# SCH_NFC-Card_2024-10-10.net
KiCad netlist of a schematic drawn in EasyEDA
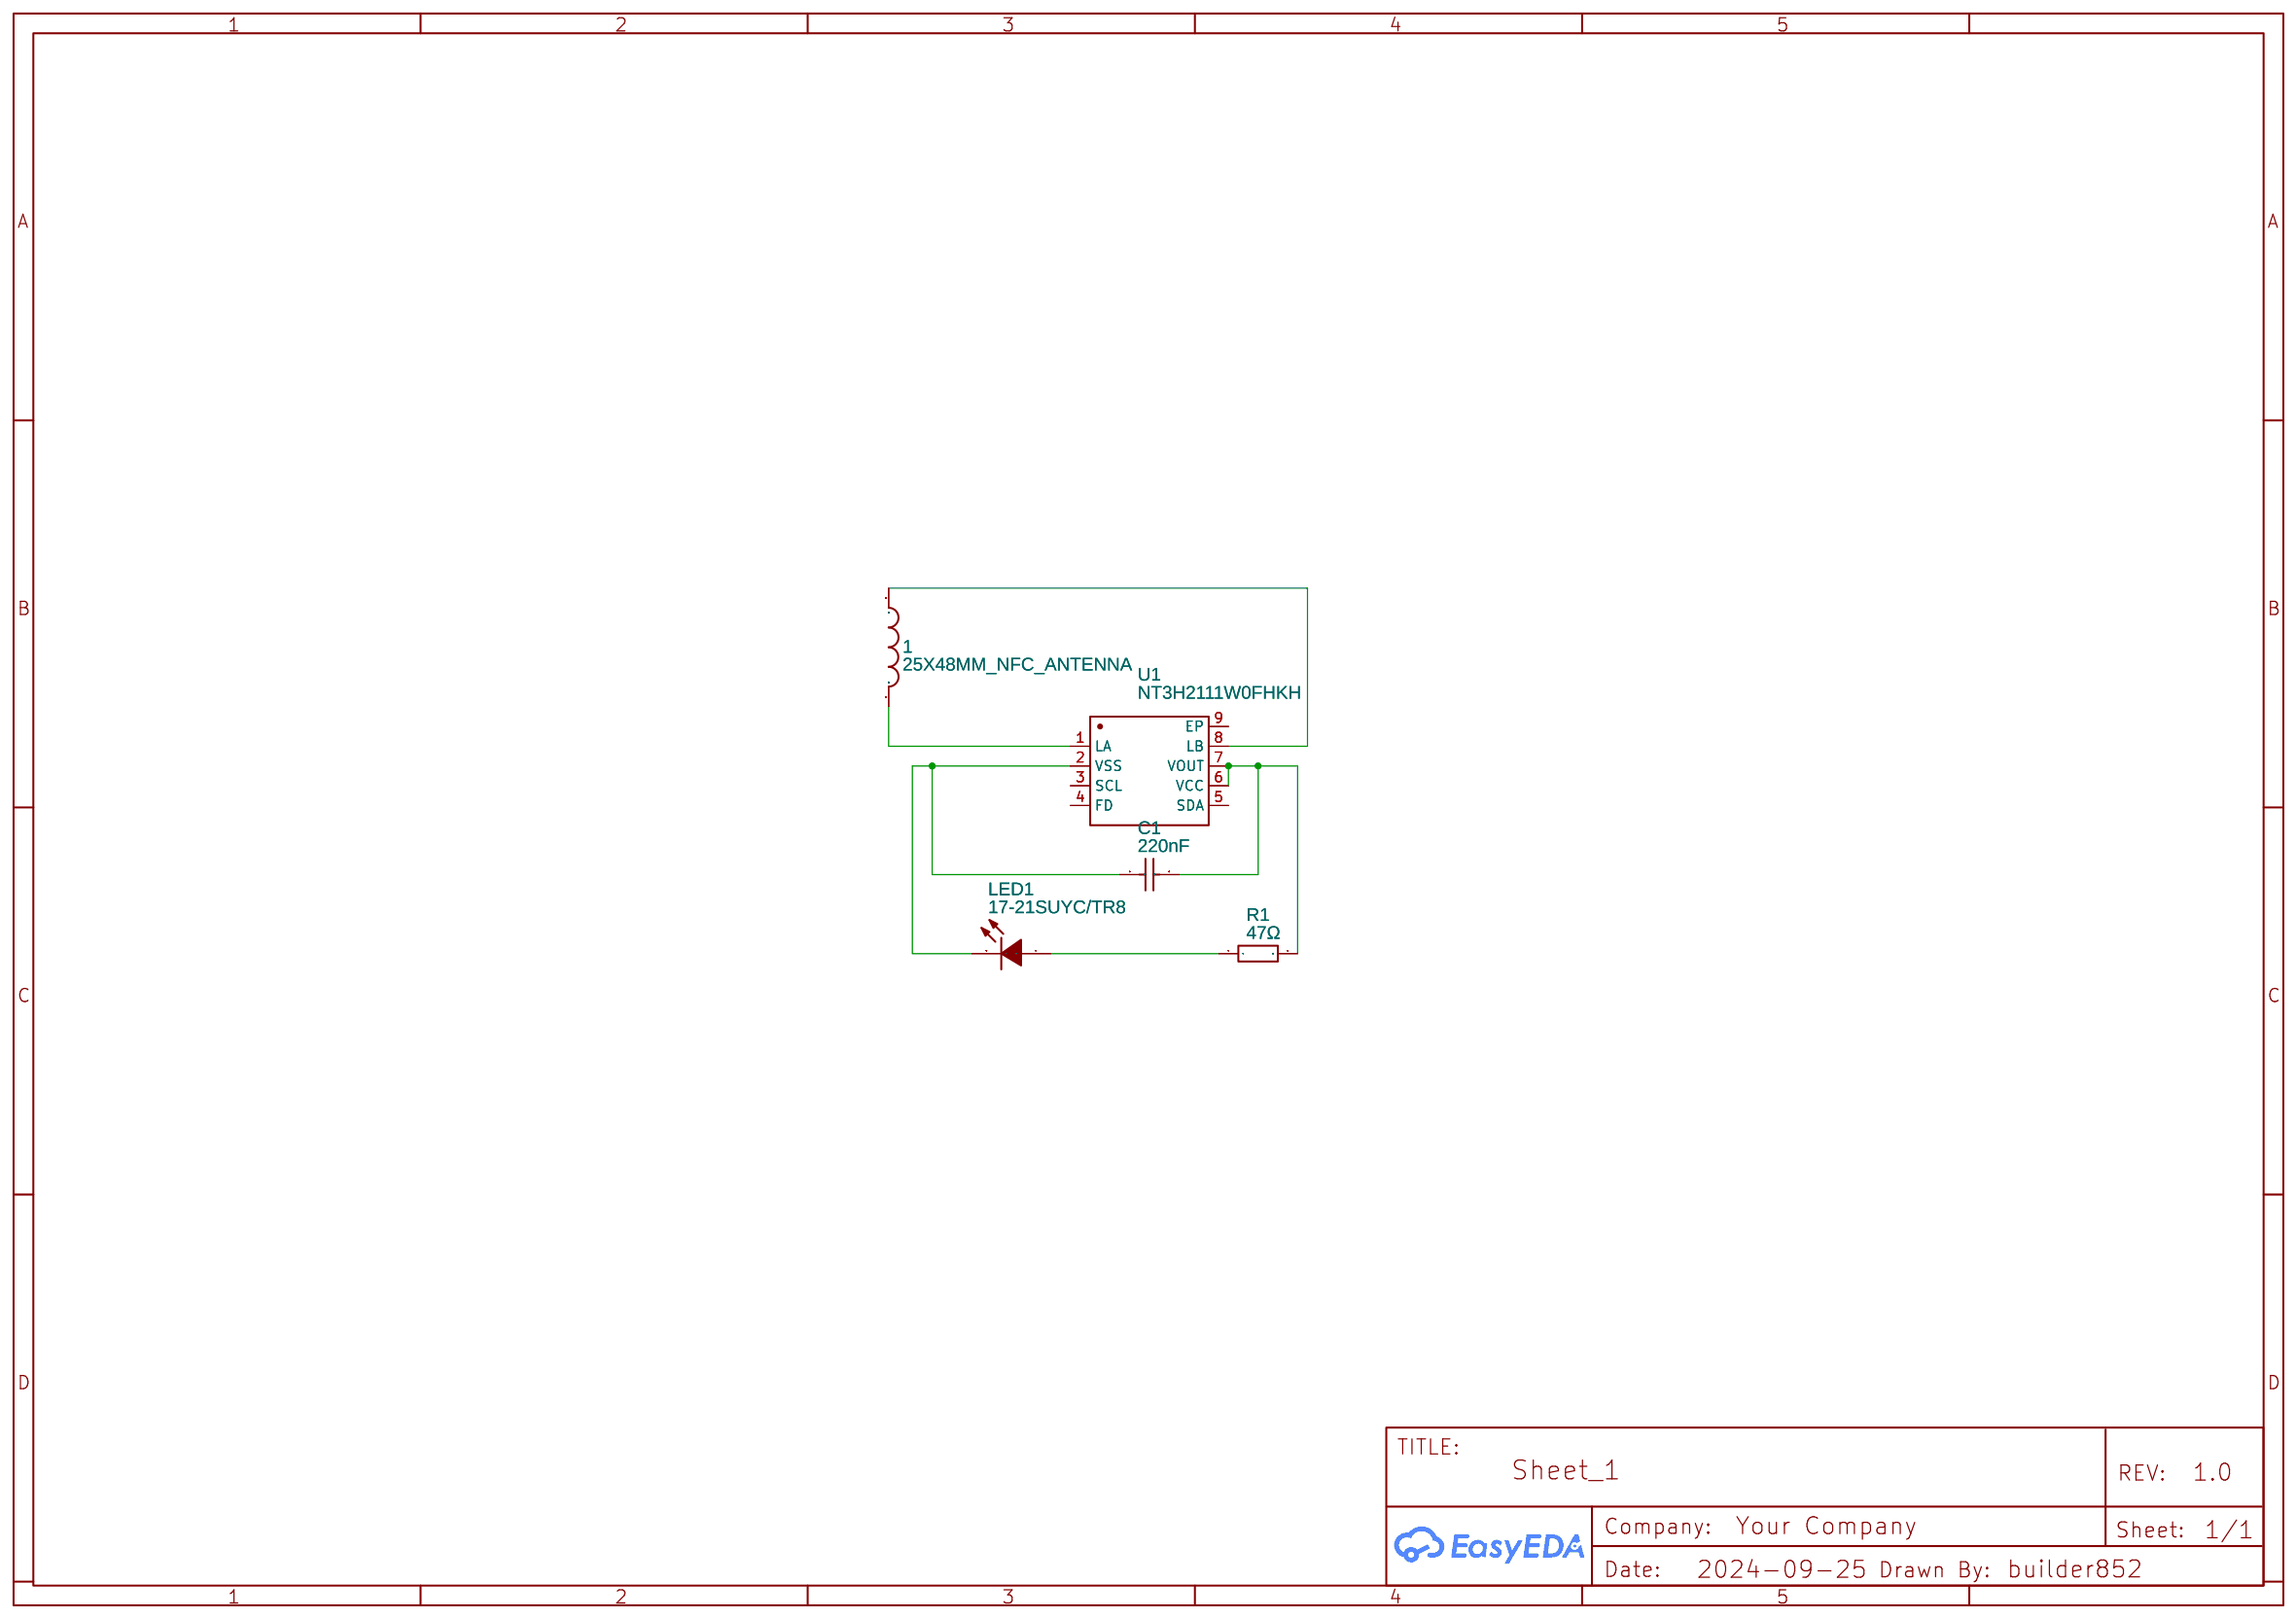
[diagram p0: schematic sheet]

(export (version "E")
  (design (tool "Eeschema 10.0.6"))
  (components
    (comp (ref "1") (value "25X48MM_NFC_ANTENNA") (libsource (lib "") (part "25X48MM_NFC_ANTENNA")))
    (comp (ref "C1")
      (value "220nF")
      (fields
        (field (name "Manufacturer Part") "CL10B224KA8NNNC")
        (field (name "Manufacturer") "SAMSUNG(三星)")
      )
      (libsource (lib "") (part "CL10B224KA8NNNC"))
    )
    (comp (ref "LED1")
      (value "17-21SUYC/TR8")
      (fields (field (name "Manufacturer Part") "KT-0805黄灯") (field (name "Manufacturer") "KENTO"))
      (libsource (lib "") (part "17-21SUYC/TR8"))
    )
    (comp (ref "R1")
      (value "47Ω")
      (fields
        (field (name "Manufacturer Part") "0603WAF470JT5E")
        (field (name "Manufacturer") "UNI-ROYAL(厚声)")
      )
      (libsource (lib "") (part "0603WAF470JT5E"))
    )
    (comp (ref "U1")
      (value "NT3H2111W0FHKH")
      (fields (field (name "Manufacturer") "NXP(恩智浦)"))
      (libsource (lib "") (part "NT3H2111W0FHKH"))
    )
  )
  (nets
    (net (code "1") (name "Net-(LED1-+)") (class "Default")
      (node (ref "LED1") (pin "1") (pinfunction "+_1") (pintype "unspecified"))
      (node (ref "R1") (pin "1") (pinfunction "1_1") (pintype "input"))
    )
    (net (code "2") (name "Net-(LED1--)") (class "Default")
      (node (ref "C1") (pin "1") (pinfunction "1_1") (pintype "input"))
      (node (ref "LED1") (pin "2") (pinfunction "-_2") (pintype "unspecified"))
      (node (ref "U1") (pin "2") (pinfunction "VSS_2") (pintype "unspecified"))
    )
    (net (code "3") (name "Net-(U1-LA)") (class "Default")
      (node (ref "1") (pin "P$2") (pinfunction "P$2_P$2") (pintype "bidirectional"))
      (node (ref "U1") (pin "1") (pinfunction "LA_1") (pintype "unspecified"))
    )
    (net (code "4") (name "Net-(U1-LB)") (class "Default")
      (node (ref "1") (pin "P$1") (pinfunction "P$1_P$1") (pintype "bidirectional"))
      (node (ref "U1") (pin "8") (pinfunction "LB_8") (pintype "unspecified"))
    )
    (net (code "5") (name "Net-(U1-VCC)") (class "Default")
      (node (ref "C1") (pin "2") (pinfunction "2_2") (pintype "input"))
      (node (ref "R1") (pin "2") (pinfunction "2_2") (pintype "input"))
      (node (ref "U1") (pin "6") (pinfunction "VCC_6") (pintype "unspecified"))
      (node (ref "U1") (pin "7") (pinfunction "VOUT_7") (pintype "unspecified"))
    )
    (net (code "6") (name "unconnected-(U1-EP-Pad9)") (class "Default")
      (node (ref "U1") (pin "9") (pinfunction "EP_9") (pintype "unspecified"))
    )
    (net (code "7") (name "unconnected-(U1-FD-Pad4)") (class "Default")
      (node (ref "U1") (pin "4") (pinfunction "FD_4") (pintype "unspecified"))
    )
    (net (code "8") (name "unconnected-(U1-SCL-Pad3)") (class "Default")
      (node (ref "U1") (pin "3") (pinfunction "SCL_3") (pintype "unspecified"))
    )
    (net (code "9") (name "unconnected-(U1-SDA-Pad5)") (class "Default")
      (node (ref "U1") (pin "5") (pinfunction "SDA_5") (pintype "unspecified"))
    )
  )
)
